# Power_supply.net
KiCad netlist of a schematic drawn in Altium Designer
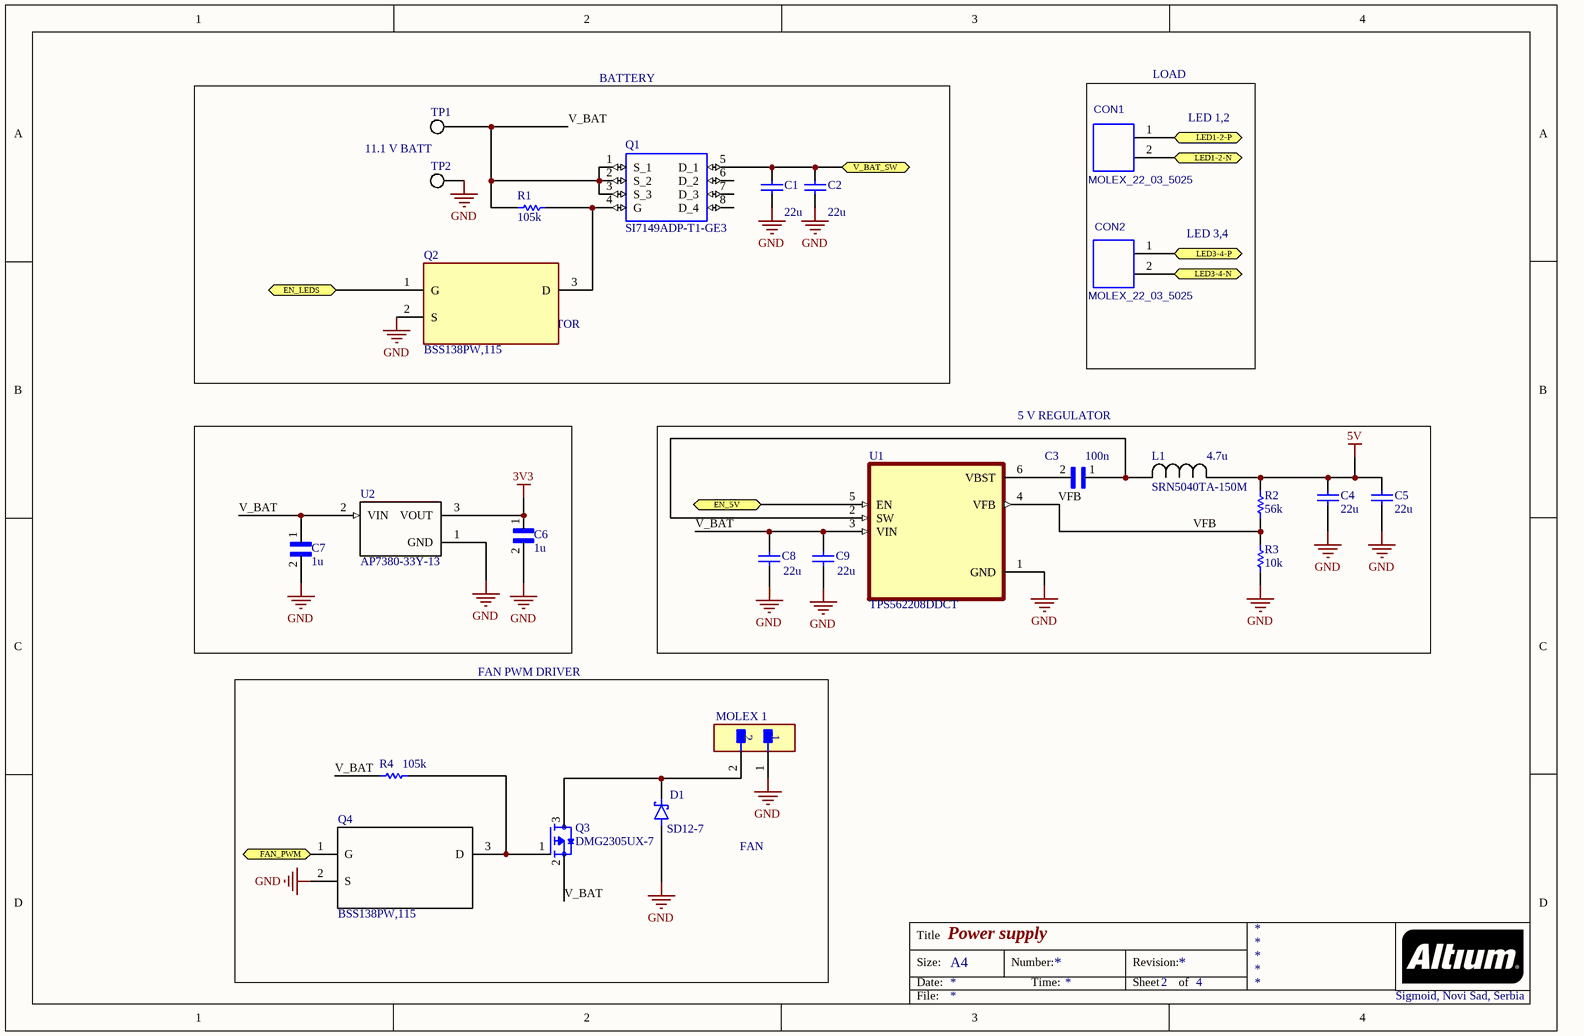
[diagram p0: Power_supply.SchDoc]

(export (version "E")
  (design (tool "Eeschema 10.0.6"))
  (components
    (comp (ref "C1")
      (value "22u")
      (footprint "Capacitor SMD 1206")
      (description "SMD Capacitor")
      (libsource (lib "Energobull Library") (part "SMD Capacitor"))
    )
    (comp (ref "C2")
      (value "22u")
      (footprint "Capacitor SMD 1206")
      (description "SMD Capacitor")
      (libsource (lib "Energobull Library") (part "SMD Capacitor"))
    )
    (comp (ref "C3")
      (value "100n")
      (footprint "CAPC0402X22N")
      (description "SMD Capacitor C0G(EIA) with Capacitance: 4.6pF Tol. 0.25pF. Rated Voltage: 25Vdc")
      (fields (field (name "MP") "GRM0225C1E4R6CA03L") (field (name "Comment") "GRM0225C1E4R6CA03L_1"))
      (libsource (lib "") (part "GRM0225C1E4R6CA03L_1_1"))
    )
    (comp (ref "C4")
      (value "22u")
      (footprint "Capacitor SMD 0603")
      (description "SMD Capacitor")
      (libsource (lib "Energobull Library") (part "SMD Capacitor"))
    )
    (comp (ref "C5")
      (value "22u")
      (footprint "Capacitor SMD 0603")
      (description "SMD Capacitor")
      (libsource (lib "Energobull Library") (part "SMD Capacitor"))
    )
    (comp (ref "C6")
      (value "1u")
      (footprint "CAPC0402X22N")
      (description "SMD Capacitor C0G(EIA) with Capacitance: 4.6pF Tol. 0.25pF. Rated Voltage: 25Vdc")
      (fields (field (name "MP") "GRM0225C1E4R6CA03L") (field (name "Comment") "GRM0225C1E4R6CA03L_1"))
      (libsource (lib "Energobull Library") (part "GRM0225C1E4R6CA03L_1"))
    )
    (comp (ref "C7")
      (value "1u")
      (footprint "CAPC0402X22N")
      (description "SMD Capacitor C0G(EIA) with Capacitance: 4.6pF Tol. 0.25pF. Rated Voltage: 25Vdc")
      (fields (field (name "MP") "GRM0225C1E4R6CA03L") (field (name "Comment") "GRM0225C1E4R6CA03L_1"))
      (libsource (lib "Energobull Library") (part "GRM0225C1E4R6CA03L_1"))
    )
    (comp (ref "C8")
      (value "22u")
      (footprint "Capacitor SMD 1206")
      (description "SMD Capacitor")
      (libsource (lib "Energobull Library") (part "SMD Capacitor"))
    )
    (comp (ref "C9")
      (value "22u")
      (footprint "Capacitor SMD 1206")
      (description "SMD Capacitor")
      (libsource (lib "Energobull Library") (part "SMD Capacitor"))
    )
    (comp (ref "CON1")
      (value "MOLEX_22_03_5025")
      (footprint "MOLEX_22-03-5025")
      (description "KONEKTOR 2 MOLEX")
      (libsource (lib "Energobull Library") (part "KONEKTOR 2-POLNI_X8Y6"))
    )
    (comp (ref "CON2")
      (value "MOLEX_22_03_5025")
      (footprint "MOLEX_22-03-5025")
      (description "KONEKTOR 2 MOLEX")
      (libsource (lib "Energobull Library") (part "KONEKTOR 2-POLNI_X8Y6"))
    )
    (comp (ref "D1")
      (value "SD12-7")
      (footprint "SOD323")
      (description "Diode, Signal, TVS, 12V, Unidir. (SOD323)")
      (fields (field (name "MP") "MBRS340") (field (name "MF") "ON Semiconductor"))
      (libsource (lib "Energobull Library") (part "MBRS340"))
    )
    (comp (ref "L1")
      (value "SRN5040TA-150M")
      (footprint "IND_A-150M")
      (description "Fixed Inductors 3.3uH 20% SMD 5040")
      (fields
        (field (name "ALTIUM_UNNAMED_1") "4.7u")
        (field (name "COPYRIGHT") "Copyright (C) 2018 Accelerated Designs. All rights reserved")
      )
      (libsource (lib "Energobull Library") (part "SRN5040TA-150M"))
    )
    (comp (ref "MOLEX 1")
      (value "CONN HEADER VERT 2POS 2MM")
      (footprint "TE_Connectivity_0_MFG")
      (description "Connector Header Through Hole 2 position 0.079\" (2.00mm)")
      (libsource (lib "Energobull Library") (part "53253-0270"))
    )
    (comp (ref "Q1")
      (value "SI7149ADP-T1-GE3")
      (footprint "POWERPAKSO-8")
      (description "P-Channel 30V 50A (Tc) 5W (Ta), 48W (Tc) Surface Mount PowerPAKÂ® SO-8")
      (fields (field (name "MF") "Vishay Siliconix"))
      (libsource (lib "Energobull Library") (part "SI7149ADP-T1-GE3"))
    )
    (comp (ref "Q2")
      (value "BSS138PW,115")
      (footprint "SOT65P210X110-3N")
      (description "N-Channel 60V 320mA _Ta_ 260mW _Ta_, 830mW _Tc_ Surface Mount SC-70")
      (fields (field (name "MF") "Nexperia USA") (field (name "DIGI-KEY_PART_NUMBER") "1727-1143-1-ND"))
      (libsource (lib "Energobull Library") (part "BSS138PW,115"))
    )
    (comp (ref "Q3")
      (value "DMG2305UX-7")
      (footprint "SOT91P240X110-3N_DMG2305UX-7 - duplicate")
      (description "P-Channel 20V 4.2A _Ta_ 1.4W _Ta_ Surface Mount SOT-23")
      (fields (field (name "MF") "Power Analog Micro"))
      (libsource (lib "Energobull Library") (part "DMG2305UX-7"))
    )
    (comp (ref "Q4")
      (value "BSS138PW,115")
      (footprint "SOT65P210X110-3N")
      (description "N-Channel 60V 320mA _Ta_ 260mW _Ta_, 830mW _Tc_ Surface Mount SC-70")
      (fields (field (name "MF") "Nexperia USA") (field (name "DIGI-KEY_PART_NUMBER") "1727-1143-1-ND"))
      (libsource (lib "Energobull Library") (part "BSS138PW,115"))
    )
    (comp (ref "R1")
      (value "SMD Resistor")
      (footprint "RESC1005X35N")
      (fields (field (name "105K") "105k"))
      (libsource (lib "Energobull Library") (part "SMD Resistor"))
    )
    (comp (ref "R2")
      (value "56k")
      (footprint "RESC1005X35N")
      (description "SMD Resistor")
      (libsource (lib "Energobull Library") (part "SMD Resistor"))
    )
    (comp (ref "R3")
      (value "10k")
      (footprint "RESC1005X35N")
      (description "SMD Resistor")
      (libsource (lib "Energobull Library") (part "SMD Resistor"))
    )
    (comp (ref "R4")
      (value "105k")
      (footprint "Resistor SMD 0603")
      (description "SMD Resistor")
      (libsource (lib "Energobull Library") (part "SMD Resistor"))
    )
    (comp (ref "TP1")
      (value "Test Point")
      (footprint "TEST POINT")
      (description "Test point")
      (libsource (lib "Energobull Library") (part "Test Point"))
    )
    (comp (ref "TP2")
      (value "Test Point")
      (footprint "TEST POINT")
      (description "Test point")
      (libsource (lib "Energobull Library") (part "Test Point"))
    )
    (comp (ref "U1")
      (value "TPS562208DDCT")
      (footprint "SOT95P280X110-6N")
      (fields (field (name "MF") "Texas Instruments"))
      (libsource (lib "Energobull Library") (part "TPS562208DDCT"))
    )
    (comp (ref "U2")
      (value "AP7380-33Y-13")
      (footprint "VREG_AP7380-33Y-13")
      (description "LDO Regulator Pos 3.3V 0.15A 4-Pin(3+Tab) SOT-89 T/R")
      (fields (field (name "MF") "Diodes Incorporated"))
      (libsource (lib "Energobull Library") (part "AP7380-33Y-13"))
    )
  )
  (nets
    (net (code "1") (name "/EN_5V") (class "Default")
      (node (ref "U1") (pin "5") (pinfunction "EN_5") (pintype "input"))
    )
    (net (code "2") (name "/EN_LEDS") (class "Default")
      (node (ref "Q2") (pin "1") (pinfunction "G_1") (pintype "passive"))
    )
    (net (code "3") (name "/FAN_PWM") (class "Default")
      (node (ref "Q4") (pin "1") (pinfunction "G_1") (pintype "passive"))
    )
    (net (code "4") (name "/LED1-2-N") (class "Default")
      (node (ref "CON1") (pin "2") (pinfunction "2_2") (pintype "passive"))
    )
    (net (code "5") (name "/LED1-2-P") (class "Default")
      (node (ref "CON1") (pin "1") (pinfunction "1_1") (pintype "passive"))
    )
    (net (code "6") (name "/LED3-4-N") (class "Default")
      (node (ref "CON2") (pin "2") (pinfunction "2_2") (pintype "passive"))
    )
    (net (code "7") (name "/LED3-4-P") (class "Default")
      (node (ref "CON2") (pin "1") (pinfunction "1_1") (pintype "passive"))
    )
    (net (code "8") (name "/VFB") (class "Default")
      (node (ref "R2") (pin "1") (pinfunction "1_1") (pintype "passive"))
      (node (ref "R3") (pin "2") (pinfunction "2_2") (pintype "passive"))
      (node (ref "U1") (pin "4") (pinfunction "VFB_4") (pintype "output"))
    )
    (net (code "9") (name "/V_BAT") (class "Default")
      (node (ref "C7") (pin "1") (pinfunction "1_1") (pintype "passive"))
      (node (ref "C8") (pin "2") (pinfunction "2_2") (pintype "passive"))
      (node (ref "C9") (pin "2") (pinfunction "2_2") (pintype "passive"))
      (node (ref "Q1") (pin "1") (pinfunction "S_1_1") (pintype "bidirectional"))
      (node (ref "Q1") (pin "2") (pinfunction "S_2_2") (pintype "bidirectional"))
      (node (ref "Q1") (pin "3") (pinfunction "S_3_3") (pintype "bidirectional"))
      (node (ref "Q3") (pin "2") (pinfunction "S_2") (pintype "passive"))
      (node (ref "R1") (pin "2") (pinfunction "2_2") (pintype "passive"))
      (node (ref "R4") (pin "1") (pinfunction "1_1") (pintype "passive"))
      (node (ref "TP1") (pin "1") (pinfunction "1_1") (pintype "passive"))
      (node (ref "U1") (pin "3") (pinfunction "VIN_3") (pintype "input"))
      (node (ref "U2") (pin "2") (pinfunction "VIN_2") (pintype "input"))
    )
    (net (code "10") (name "/V_BAT_SW") (class "Default")
      (node (ref "C1") (pin "2") (pinfunction "2_2") (pintype "passive"))
      (node (ref "C2") (pin "2") (pinfunction "2_2") (pintype "passive"))
      (node (ref "Q1") (pin "5") (pinfunction "D_1_5") (pintype "bidirectional"))
    )
    (net (code "11") (name "3V3") (class "Default")
      (node (ref "C6") (pin "1") (pinfunction "1_1") (pintype "passive"))
      (node (ref "U2") (pin "3") (pinfunction "VOUT_3") (pintype "power_in"))
    )
    (net (code "12") (name "5V") (class "Default")
      (node (ref "C4") (pin "2") (pinfunction "2_2") (pintype "passive"))
      (node (ref "C5") (pin "2") (pinfunction "2_2") (pintype "passive"))
      (node (ref "L1") (pin "1") (pinfunction "1_1") (pintype "passive"))
      (node (ref "R2") (pin "2") (pinfunction "2_2") (pintype "passive"))
    )
    (net (code "13") (name "GND") (class "Default")
      (node (ref "C1") (pin "1") (pinfunction "1_1") (pintype "passive"))
      (node (ref "C2") (pin "1") (pinfunction "1_1") (pintype "passive"))
      (node (ref "C4") (pin "1") (pinfunction "1_1") (pintype "passive"))
      (node (ref "C5") (pin "1") (pinfunction "1_1") (pintype "passive"))
      (node (ref "C6") (pin "2") (pinfunction "2_2") (pintype "passive"))
      (node (ref "C7") (pin "2") (pinfunction "2_2") (pintype "passive"))
      (node (ref "C8") (pin "1") (pinfunction "1_1") (pintype "passive"))
      (node (ref "C9") (pin "1") (pinfunction "1_1") (pintype "passive"))
      (node (ref "D1") (pin "A") (pinfunction "A_A") (pintype "passive"))
      (node (ref "MOLEX 1") (pin "1") (pinfunction "1_1") (pintype "passive"))
      (node (ref "Q2") (pin "2") (pinfunction "S_2") (pintype "passive"))
      (node (ref "Q4") (pin "2") (pinfunction "S_2") (pintype "passive"))
      (node (ref "R3") (pin "1") (pinfunction "1_1") (pintype "passive"))
      (node (ref "TP2") (pin "1") (pinfunction "1_1") (pintype "passive"))
      (node (ref "U1") (pin "1") (pinfunction "GND_1") (pintype "power_in"))
      (node (ref "U2") (pin "1") (pinfunction "GND_1") (pintype "power_in"))
    )
    (net (code "14") (name "Net-(D1-K)") (class "Default")
      (node (ref "D1") (pin "C") (pinfunction "K_C") (pintype "passive"))
      (node (ref "MOLEX 1") (pin "2") (pinfunction "2_2") (pintype "passive"))
      (node (ref "Q3") (pin "3") (pinfunction "D_3") (pintype "passive"))
    )
    (net (code "15") (name "Net-(Q1-G)") (class "Default")
      (node (ref "Q1") (pin "4") (pinfunction "G_4") (pintype "bidirectional"))
      (node (ref "Q2") (pin "3") (pinfunction "D_3") (pintype "passive"))
      (node (ref "R1") (pin "1") (pinfunction "1_1") (pintype "passive"))
    )
    (net (code "16") (name "Net-(Q3-G)") (class "Default")
      (node (ref "Q3") (pin "1") (pinfunction "G_1") (pintype "passive"))
      (node (ref "Q4") (pin "3") (pinfunction "D_3") (pintype "passive"))
      (node (ref "R4") (pin "2") (pinfunction "2_2") (pintype "passive"))
    )
    (net (code "17") (name "Net-(U1-SW)") (class "Default")
      (node (ref "C3") (pin "1") (pinfunction "1_1") (pintype "passive"))
      (node (ref "L1") (pin "2") (pinfunction "2_2") (pintype "passive"))
      (node (ref "U1") (pin "2") (pinfunction "SW_2") (pintype "input"))
    )
    (net (code "18") (name "Net-(U1-VBST)") (class "Default")
      (node (ref "C3") (pin "2") (pinfunction "2_2") (pintype "passive"))
      (node (ref "U1") (pin "6") (pinfunction "VBST_6") (pintype "power_in"))
    )
    (net (code "19") (name "unconnected-(Q1-D_2-Pad6)") (class "Default")
      (node (ref "Q1") (pin "6") (pinfunction "D_2_6") (pintype "bidirectional"))
    )
    (net (code "20") (name "unconnected-(Q1-D_3-Pad7)") (class "Default")
      (node (ref "Q1") (pin "7") (pinfunction "D_3_7") (pintype "bidirectional"))
    )
    (net (code "21") (name "unconnected-(Q1-D_4-Pad8)") (class "Default")
      (node (ref "Q1") (pin "8") (pinfunction "D_4_8") (pintype "bidirectional"))
    )
  )
)
